# USB_IFC.net
KiCad netlist of a schematic drawn in Altium Designer
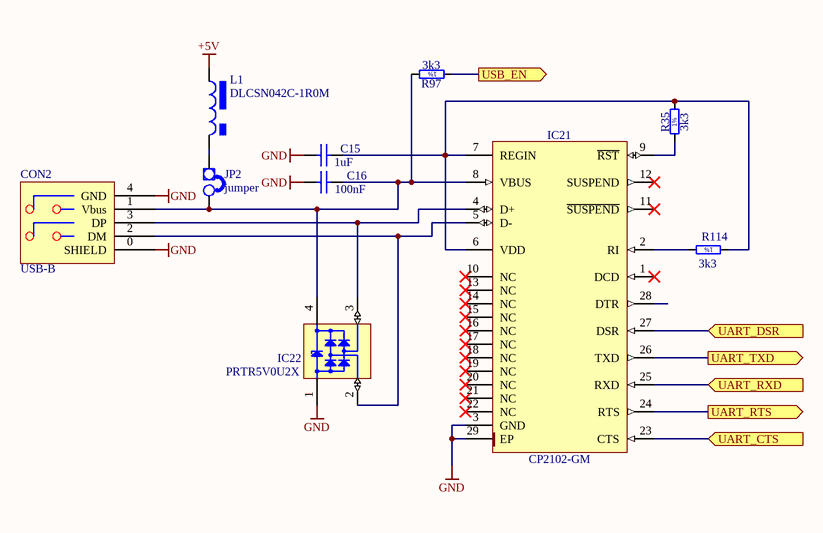
[diagram p0: USB_IFC.SchDoc]

(export (version "E")
  (design (tool "Eeschema 10.0.6"))
  (components
    (comp (ref "C15")
      (value "1uF")
      (footprint "0603C")
      (description "Non-polarised capacitor")
      (fields
        (field (name "PART NUMBER") "CC0603_1UF_16V_10%_X7R")
        (field (name "VOLTAGE") "16V")
        (field (name "AUTHOR") "CERN DEM JLC")
      )
      (libsource (lib "Capacitors") (part "Capacitor - non polarized"))
    )
    (comp (ref "C16")
      (value "100nF")
      (footprint "0603C")
      (description "Non-polarised capacitor")
      (fields
        (field (name "PART NUMBER") "CC0603_100NF_50V_10%_X7R")
        (field (name "VOLTAGE") "50V")
        (field (name "AUTHOR") "CERN DEM JLC")
      )
      (libsource (lib "Capacitors") (part "Capacitor - non polarized"))
    )
    (comp (ref "CON2")
      (value "USB-B")
      (footprint "USBB-G")
      (description "USB connector B type (TME)")
      (libsource (lib "LIBRARY_SCH") (part "CON_USB_B"))
    )
    (comp (ref "IC21")
      (value "CP2102-GM")
      (footprint "QFN50P500X500X100-29N-S335")
      (description "Single-Chip USB to UART Bridge")
      (fields (field (name "MANUFACTURER") "SILICON LABS") (field (name "AUTHOR") "CERN DEM JLC"))
      (libsource (lib "ICs And Semiconductors") (part "CP2102-GM"))
    )
    (comp (ref "IC22")
      (value "PRTR5V0U2X")
      (footprint "SOT190P230X110-4N")
      (description "Ultra Low Capacitance Double Rail-to-Rail ESD Protection Diode")
      (fields
        (field (name "VOLTAGE") "5.5V")
        (field (name "MANUFACTURER") "PHILIPS NXP")
        (field (name "AUTHOR") "CERN DEM JLC")
      )
      (libsource (lib "ICs And Semiconductors") (part "PRTR5V0U2X"))
    )
    (comp (ref "JP2")
      (value "jumper")
      (footprint "jump")
      (description "Jumper")
      (libsource (lib "LIBRARY_SCH") (part "JUMPER"))
    )
    (comp (ref "L1")
      (value "DLCSN042C-1R0M")
      (footprint "L_DLCSN042C")
      (description "inductor (Maritex)")
      (libsource (lib "LIBRARY_SCH") (part "L_POWER_DLCSN042C"))
    )
    (comp (ref "R35")
      (value "3k3")
      (footprint "0603R")
      (description "Resistor - 1%")
      (fields
        (field (name "PART NUMBER") "R0603_3K3_1%_0.1W_100PPM")
        (field (name "POWER") "0.1W")
        (field (name "AUTHOR") "CERN DEM JLC")
      )
      (libsource (lib "Resistors") (part "Resistor - 1%"))
    )
    (comp (ref "R97")
      (value "3k3")
      (footprint "0603R")
      (description "Resistor - 1%")
      (fields
        (field (name "PART NUMBER") "R0603_3K3_1%_0.1W_100PPM")
        (field (name "POWER") "0.1W")
        (field (name "AUTHOR") "CERN DEM JLC")
      )
      (libsource (lib "Resistors") (part "Resistor - 1%"))
    )
    (comp (ref "R114")
      (value "3k3")
      (footprint "0603R")
      (description "Resistor - 1%")
      (fields
        (field (name "PART NUMBER") "R0603_3K3_1%_0.1W_100PPM")
        (field (name "POWER") "0.1W")
        (field (name "AUTHOR") "CERN DEM JLC")
      )
      (libsource (lib "Resistors") (part "Resistor - 1%"))
    )
  )
  (nets
    (net (code "1") (name "+5V") (class "Default") (node (ref "L1") (pin "1") (pintype "passive")))
    (net (code "2") (name "/UART_CTS") (class "Default")
      (node (ref "IC21") (pin "23") (pinfunction "CTS_23") (pintype "input"))
    )
    (net (code "3") (name "/UART_DSR") (class "Default")
      (node (ref "IC21") (pin "27") (pinfunction "DSR_27") (pintype "input"))
    )
    (net (code "4") (name "/UART_RTS") (class "Default")
      (node (ref "IC21") (pin "24") (pinfunction "RTS_24") (pintype "output"))
    )
    (net (code "5") (name "/UART_RXD") (class "Default")
      (node (ref "IC21") (pin "25") (pinfunction "RXD_25") (pintype "input"))
    )
    (net (code "6") (name "/UART_TXD") (class "Default")
      (node (ref "IC21") (pin "26") (pinfunction "TXD_26") (pintype "output"))
    )
    (net (code "7") (name "/USB_EN") (class "Default")
      (node (ref "R97") (pin "1") (pinfunction "1_1") (pintype "passive"))
    )
    (net (code "8") (name "GND") (class "Default")
      (node (ref "C15") (pin "2") (pinfunction "2_2") (pintype "passive"))
      (node (ref "C16") (pin "2") (pinfunction "2_2") (pintype "passive"))
      (node (ref "CON2") (pin "0") (pinfunction "SHIELD_0") (pintype "passive"))
      (node (ref "CON2") (pin "4") (pinfunction "GND_4") (pintype "passive"))
      (node (ref "IC21") (pin "29") (pinfunction "EP_29") (pintype "power_in"))
      (node (ref "IC21") (pin "3") (pinfunction "GND_3") (pintype "power_in"))
      (node (ref "IC22") (pin "1") (pinfunction "GND_1") (pintype "power_in"))
    )
    (net (code "9") (name "Net-(CON2-DM)") (class "Default")
      (node (ref "CON2") (pin "2") (pinfunction "DM_2") (pintype "passive"))
      (node (ref "IC21") (pin "5") (pinfunction "D-_5") (pintype "bidirectional"))
      (node (ref "IC22") (pin "2") (pinfunction "I/O1_2") (pintype "bidirectional"))
    )
    (net (code "10") (name "Net-(CON2-DP)") (class "Default")
      (node (ref "CON2") (pin "3") (pinfunction "DP_3") (pintype "passive"))
      (node (ref "IC21") (pin "4") (pinfunction "D+_4") (pintype "bidirectional"))
      (node (ref "IC22") (pin "3") (pinfunction "I/O2_3") (pintype "bidirectional"))
    )
    (net (code "11") (name "Net-(CON2-Vbus)") (class "Default")
      (node (ref "C16") (pin "1") (pinfunction "1_1") (pintype "passive"))
      (node (ref "CON2") (pin "1") (pinfunction "Vbus_1") (pintype "passive"))
      (node (ref "IC21") (pin "8") (pinfunction "VBUS_8") (pintype "input"))
      (node (ref "IC22") (pin "4") (pinfunction "VCC_4") (pintype "power_in"))
      (node (ref "JP2") (pin "2") (pinfunction "E2_2") (pintype "passive"))
      (node (ref "R97") (pin "2") (pinfunction "2_2") (pintype "passive"))
    )
    (net (code "12") (name "Net-(IC21-REGIN)") (class "Default")
      (node (ref "C15") (pin "1") (pinfunction "1_1") (pintype "passive"))
      (node (ref "IC21") (pin "6") (pinfunction "VDD_6") (pintype "power_in"))
      (node (ref "IC21") (pin "7") (pinfunction "REGIN_7") (pintype "power_in"))
      (node (ref "R114") (pin "1") (pinfunction "1_1") (pintype "passive"))
      (node (ref "R35") (pin "2") (pinfunction "2_2") (pintype "passive"))
    )
    (net (code "13") (name "Net-(IC21-RI)") (class "Default")
      (node (ref "IC21") (pin "2") (pinfunction "RI_2") (pintype "input"))
      (node (ref "R114") (pin "2") (pinfunction "2_2") (pintype "passive"))
    )
    (net (code "14") (name "Net-(IC21-~{RST})") (class "Default")
      (node (ref "IC21") (pin "9") (pinfunction "~{RST}_9") (pintype "bidirectional"))
      (node (ref "R35") (pin "1") (pinfunction "1_1") (pintype "passive"))
    )
    (net (code "15") (name "Net-(JP2-E1)") (class "Default")
      (node (ref "JP2") (pin "1") (pinfunction "E1_1") (pintype "passive"))
      (node (ref "L1") (pin "2") (pintype "passive"))
    )
    (net (code "16") (name "unconnected-(IC21-DCD-Pad1)") (class "Default")
      (node (ref "IC21") (pin "1") (pinfunction "DCD_1") (pintype "input+no_connect"))
    )
    (net (code "17") (name "unconnected-(IC21-DTR-Pad28)") (class "Default")
      (node (ref "IC21") (pin "28") (pinfunction "DTR_28") (pintype "output"))
    )
    (net (code "18") (name "unconnected-(IC21-NC-Pad10)") (class "Default")
      (node (ref "IC21") (pin "10") (pinfunction "NC_10") (pintype "passive+no_connect"))
    )
    (net (code "19") (name "unconnected-(IC21-NC-Pad13)") (class "Default")
      (node (ref "IC21") (pin "13") (pinfunction "NC_13") (pintype "passive+no_connect"))
    )
    (net (code "20") (name "unconnected-(IC21-NC-Pad14)") (class "Default")
      (node (ref "IC21") (pin "14") (pinfunction "NC_14") (pintype "passive+no_connect"))
    )
    (net (code "21") (name "unconnected-(IC21-NC-Pad15)") (class "Default")
      (node (ref "IC21") (pin "15") (pinfunction "NC_15") (pintype "passive+no_connect"))
    )
    (net (code "22") (name "unconnected-(IC21-NC-Pad16)") (class "Default")
      (node (ref "IC21") (pin "16") (pinfunction "NC_16") (pintype "passive+no_connect"))
    )
    (net (code "23") (name "unconnected-(IC21-NC-Pad17)") (class "Default")
      (node (ref "IC21") (pin "17") (pinfunction "NC_17") (pintype "passive+no_connect"))
    )
    (net (code "24") (name "unconnected-(IC21-NC-Pad18)") (class "Default")
      (node (ref "IC21") (pin "18") (pinfunction "NC_18") (pintype "passive+no_connect"))
    )
    (net (code "25") (name "unconnected-(IC21-NC-Pad19)") (class "Default")
      (node (ref "IC21") (pin "19") (pinfunction "NC_19") (pintype "passive+no_connect"))
    )
    (net (code "26") (name "unconnected-(IC21-NC-Pad20)") (class "Default")
      (node (ref "IC21") (pin "20") (pinfunction "NC_20") (pintype "passive+no_connect"))
    )
    (net (code "27") (name "unconnected-(IC21-NC-Pad21)") (class "Default")
      (node (ref "IC21") (pin "21") (pinfunction "NC_21") (pintype "passive+no_connect"))
    )
    (net (code "28") (name "unconnected-(IC21-NC-Pad22)") (class "Default")
      (node (ref "IC21") (pin "22") (pinfunction "NC_22") (pintype "passive+no_connect"))
    )
    (net (code "29") (name "unconnected-(IC21-SUSPEND-Pad12)") (class "Default")
      (node (ref "IC21") (pin "12") (pinfunction "SUSPEND_12") (pintype "output+no_connect"))
    )
    (net (code "30") (name "unconnected-(IC21-~{SUSPEND}-Pad11)") (class "Default")
      (node (ref "IC21") (pin "11") (pinfunction "~{SUSPEND}_11") (pintype "output+no_connect"))
    )
  )
)
